# c1yc_ldm.net
KiCad netlist of a schematic drawn in Altium Designer
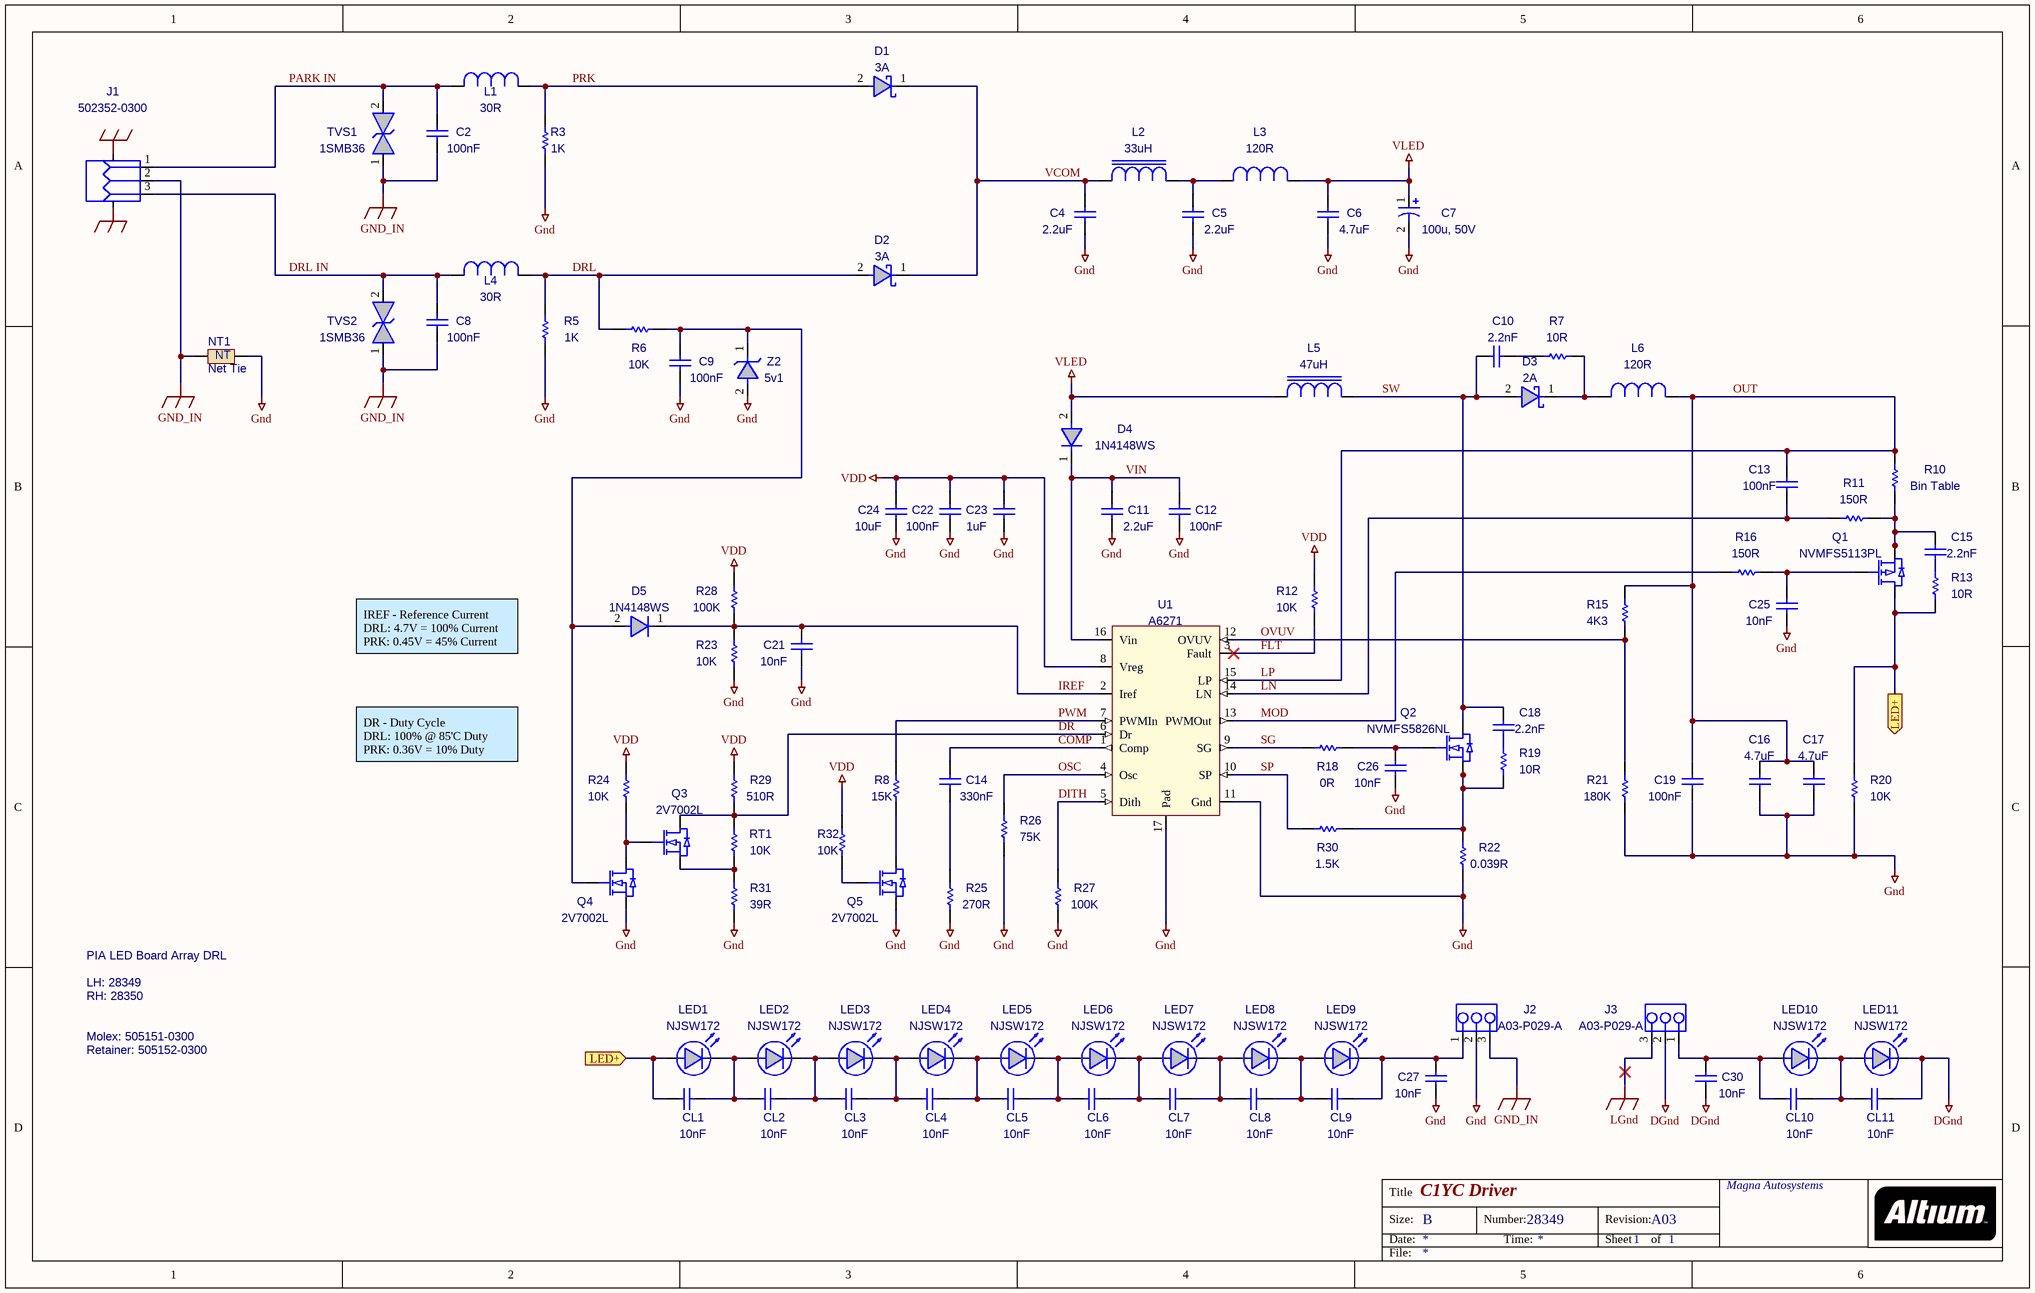
[diagram p0: c1yc_ldm.SchDoc]

(export (version "E")
  (design (tool "Eeschema 10.0.6"))
  (components
    (comp (ref "C2")
      (value "100nF")
      (footprint "CAPC0603(1608)100_N")
      (description "CAP 100nF 50V ±10% 0603 (1608 Metric) Thickness 1mm SMD")
      (fields (field (name "TOLERANCE") "±10%"))
      (libsource (lib "Altium Content Vault") (part "CMP-1035-02592-1"))
    )
    (comp (ref "C4")
      (value "2.2uF")
      (footprint "CAPC1210(3225)230_N")
      (description "CAP 2.2uF 35V ±20% 1210 (3225 Metric) Thickness 2.3mm SMD")
      (fields (field (name "TOLERANCE") "±20%"))
      (libsource (lib "Altium Content Vault") (part "CMP-1038-02095-1"))
    )
    (comp (ref "C5")
      (value "2.2uF")
      (footprint "CAPC1210(3225)230_N")
      (description "CAP 2.2uF 35V ±20% 1210 (3225 Metric) Thickness 2.3mm SMD")
      (fields (field (name "TOLERANCE") "±20%"))
      (libsource (lib "Altium Content Vault") (part "CMP-1038-02095-1"))
    )
    (comp (ref "C6")
      (value "4.7uF")
      (footprint "CAPC1210(3225)280_N")
      (description "CAP 4.7uF 50V ±10% 1210 (3225 Metric) Thickness 2.8mm SMD")
      (fields (field (name "TOLERANCE") "±10%"))
      (libsource (lib "Altium Content Vault") (part "CMP-1038-02162-1"))
    )
    (comp (ref "C7")
      (value "100u, 50V")
      (footprint "146CT1 Series 1010")
      (description "CAP ALUM 100UF 50V 20% SMD 1010")
      (libsource (lib "as_new") (part "Cap_Electro_Vishay"))
    )
    (comp (ref "C8")
      (value "100nF")
      (footprint "CAPC0603(1608)100_N")
      (description "CAP 100nF 50V ±10% 0603 (1608 Metric) Thickness 1mm SMD")
      (fields (field (name "TOLERANCE") "±10%"))
      (libsource (lib "Altium Content Vault") (part "CMP-1035-02592-1"))
    )
    (comp (ref "C9")
      (value "100nF")
      (footprint "CAPC0603(1608)100_N")
      (description "CAP 100nF 50V ±10% 0603 (1608 Metric) Thickness 1mm SMD")
      (fields (field (name "TOLERANCE") "±10%"))
      (libsource (lib "Altium Content Vault") (part "CMP-1035-02592-1"))
    )
    (comp (ref "C10")
      (value "2.2nF")
      (footprint "CAPC0603(1608)100_N")
      (description "CAP 2.2nF 50V ±10% 0603 (1608 Metric) Thickness 1mm SMD")
      (fields (field (name "TOLERANCE") "±10%"))
      (libsource (lib "Altium Content Vault") (part "CMP-1035-02039-1"))
    )
    (comp (ref "C11")
      (value "2.2uF")
      (footprint "CAPC1210(3225)230_N")
      (description "CAP 2.2uF 35V ±20% 1210 (3225 Metric) Thickness 2.3mm SMD")
      (fields (field (name "TOLERANCE") "±20%"))
      (libsource (lib "Altium Content Vault") (part "CMP-1038-02095-1"))
    )
    (comp (ref "C12")
      (value "100nF")
      (footprint "CAPC0603(1608)100_N")
      (description "CAP 100nF 50V ±10% 0603 (1608 Metric) Thickness 1mm SMD")
      (fields (field (name "TOLERANCE") "±10%"))
      (libsource (lib "Altium Content Vault") (part "CMP-1035-02592-1"))
    )
    (comp (ref "C13")
      (value "100nF")
      (footprint "CAPC0603(1608)100_N")
      (description "CAP 100nF 50V ±10% 0603 (1608 Metric) Thickness 1mm SMD")
      (fields (field (name "TOLERANCE") "±10%"))
      (libsource (lib "Altium Content Vault") (part "CMP-1035-02592-1"))
    )
    (comp (ref "C14")
      (value "330nF")
      (footprint "CAPC0603(1608)100_N")
      (description "CAP330nF 50V ±10% 0603 (1608 Metric) Thickness 1mm SMD")
      (fields (field (name "TOLERANCE") "±10%"))
      (libsource (lib "Altium Content Vault") (part "CMP-1035-02321-1"))
    )
    (comp (ref "C15")
      (value "2.2nF")
      (footprint "CAPC0603(1608)100_N")
      (description "CAP 2.2nF 50V ±10% 0603 (1608 Metric) Thickness 1mm SMD")
      (fields (field (name "TOLERANCE") "±10%"))
      (libsource (lib "Altium Content Vault") (part "CAP"))
    )
    (comp (ref "C16")
      (value "4.7uF")
      (footprint "CAPC1210(3225)280_N")
      (description "CAP 4.7uF 50V ±10% 1210 (3225 Metric) Thickness 2.8mm SMD")
      (fields (field (name "TOLERANCE") "±10%"))
      (libsource (lib "Altium Content Vault") (part "CMP-1038-02162-1"))
    )
    (comp (ref "C17")
      (value "4.7uF")
      (footprint "CAPC1210(3225)280_N")
      (description "CAP 4.7uF 50V ±10% 1210 (3225 Metric) Thickness 2.8mm SMD")
      (fields (field (name "TOLERANCE") "±10%"))
      (libsource (lib "Altium Content Vault") (part "CMP-1038-02162-1"))
    )
    (comp (ref "C18")
      (value "2.2nF")
      (footprint "CAPC0603(1608)100_N")
      (description "CAP 2.2nF 50V ±10% 0603 (1608 Metric) Thickness 1mm SMD")
      (fields (field (name "TOLERANCE") "±10%"))
      (libsource (lib "Altium Content Vault") (part "CAP"))
    )
    (comp (ref "C19")
      (value "100nF")
      (footprint "CAPC0603(1608)100_N")
      (description "CAP 100nF 50V ±10% 0603 (1608 Metric) Thickness 1mm SMD")
      (fields (field (name "TOLERANCE") "±10%"))
      (libsource (lib "Altium Content Vault") (part "CMP-1035-02592-1"))
    )
    (comp (ref "C21")
      (value "10nF")
      (footprint "CAPC0603(1608)100_N")
      (description "CAP 10nF 50V ±10% 0603 (1608 Metric) Thickness 1mm SMD")
      (fields (field (name "TOLERANCE") "±10%"))
      (libsource (lib "Altium Content Vault") (part "CMP-1035-02321-1"))
    )
    (comp (ref "C22")
      (value "100nF")
      (footprint "CAPC0603(1608)100_N")
      (description "CAP 100nF 50V ±10% 0603 (1608 Metric) Thickness 1mm SMD")
      (fields (field (name "TOLERANCE") "±10%"))
      (libsource (lib "Altium Content Vault") (part "CMP-1035-02592-1"))
    )
    (comp (ref "C23")
      (value "1uF")
      (footprint "CAPC0603(1608)100_N")
      (description "CAP 1uF 35V ±10% 0603 (1608 Metric) Thickness 1mm SMD")
      (fields (field (name "TOLERANCE") "±10%"))
      (libsource (lib "Altium Content Vault") (part "CMP-1035-02706-1"))
    )
    (comp (ref "C24")
      (value "10uF")
      (footprint "CAPC1206(3216)190_L")
      (description "CAP 10uF 16V ±10% 1206 (3216 Metric) Thickness 1.9mm SMD")
      (fields (field (name "TOLERANCE") "±10%"))
      (libsource (lib "Altium Content Vault") (part "CMP-1037-04974-1"))
    )
    (comp (ref "C25")
      (value "10nF")
      (footprint "CAPC0603(1608)100_N")
      (description "CAP 10nF 50V ±10% 0603 (1608 Metric) Thickness 1mm SMD")
      (fields (field (name "TOLERANCE") "±10%"))
      (libsource (lib "Altium Content Vault") (part "CMP-1035-02321-1"))
    )
    (comp (ref "C26")
      (value "10nF")
      (footprint "CAPC0603(1608)100_N")
      (description "CAP 10nF 50V ±10% 0603 (1608 Metric) Thickness 1mm SMD")
      (fields (field (name "TOLERANCE") "±10%"))
      (libsource (lib "Altium Content Vault") (part "CMP-1035-02321-1"))
    )
    (comp (ref "C27")
      (value "10nF")
      (footprint "CAPC0603(1608)100_N")
      (description "CAP 10nF 50V ±10% 0603 (1608 Metric) Thickness 1mm SMD")
      (fields (field (name "TOLERANCE") "±10%"))
      (libsource (lib "Altium Content Vault") (part "CMP-1035-02321-1"))
    )
    (comp (ref "C30")
      (value "10nF")
      (footprint "CAPC0603(1608)100_N")
      (description "CAP 10nF 50V ±10% 0603 (1608 Metric) Thickness 1mm SMD")
      (fields (field (name "TOLERANCE") "±10%"))
      (libsource (lib "Altium Content Vault") (part "CMP-1035-02321-1"))
    )
    (comp (ref "CL1")
      (value "10nF")
      (footprint "CAPC0603(1608)100_N")
      (description "CAP 10nF 50V ±10% 0603 (1608 Metric) Thickness 1mm SMD")
      (fields (field (name "TOLERANCE") "±10%"))
      (libsource (lib "Altium Content Vault") (part "CMP-1035-02321-1"))
    )
    (comp (ref "CL2")
      (value "10nF")
      (footprint "CAPC0603(1608)100_N")
      (description "CAP 10nF 50V ±10% 0603 (1608 Metric) Thickness 1mm SMD")
      (fields (field (name "TOLERANCE") "±10%"))
      (libsource (lib "Altium Content Vault") (part "CMP-1035-02321-1"))
    )
    (comp (ref "CL3")
      (value "10nF")
      (footprint "CAPC0603(1608)100_N")
      (description "CAP 10nF 50V ±10% 0603 (1608 Metric) Thickness 1mm SMD")
      (fields (field (name "TOLERANCE") "±10%"))
      (libsource (lib "Altium Content Vault") (part "CMP-1035-02321-1"))
    )
    (comp (ref "CL4")
      (value "10nF")
      (footprint "CAPC0603(1608)100_N")
      (description "CAP 10nF 50V ±10% 0603 (1608 Metric) Thickness 1mm SMD")
      (fields (field (name "TOLERANCE") "±10%"))
      (libsource (lib "Altium Content Vault") (part "CMP-1035-02321-1"))
    )
    (comp (ref "CL5")
      (value "10nF")
      (footprint "CAPC0603(1608)100_N")
      (description "CAP 10nF 50V ±10% 0603 (1608 Metric) Thickness 1mm SMD")
      (fields (field (name "TOLERANCE") "±10%"))
      (libsource (lib "Altium Content Vault") (part "CMP-1035-02321-1"))
    )
    (comp (ref "CL6")
      (value "10nF")
      (footprint "CAPC0603(1608)100_N")
      (description "CAP 10nF 50V ±10% 0603 (1608 Metric) Thickness 1mm SMD")
      (fields (field (name "TOLERANCE") "±10%"))
      (libsource (lib "Altium Content Vault") (part "CMP-1035-02321-1"))
    )
    (comp (ref "CL7")
      (value "10nF")
      (footprint "CAPC0603(1608)100_N")
      (description "CAP 10nF 50V ±10% 0603 (1608 Metric) Thickness 1mm SMD")
      (fields (field (name "TOLERANCE") "±10%"))
      (libsource (lib "Altium Content Vault") (part "CMP-1035-02321-1"))
    )
    (comp (ref "CL8")
      (value "10nF")
      (footprint "CAPC0603(1608)100_N")
      (description "CAP 10nF 50V ±10% 0603 (1608 Metric) Thickness 1mm SMD")
      (fields (field (name "TOLERANCE") "±10%"))
      (libsource (lib "Altium Content Vault") (part "CMP-1035-02321-1"))
    )
    (comp (ref "CL9")
      (value "10nF")
      (footprint "CAPC0603(1608)100_N")
      (description "CAP 10nF 50V ±10% 0603 (1608 Metric) Thickness 1mm SMD")
      (fields (field (name "TOLERANCE") "±10%"))
      (libsource (lib "Altium Content Vault") (part "CMP-1035-02321-1"))
    )
    (comp (ref "CL10")
      (value "10nF")
      (footprint "CAPC0603(1608)100_N")
      (description "CAP 10nF 50V ±10% 0603 (1608 Metric) Thickness 1mm SMD")
      (fields (field (name "TOLERANCE") "±10%"))
      (libsource (lib "Altium Content Vault") (part "CMP-1035-02321-1"))
    )
    (comp (ref "CL11")
      (value "10nF")
      (footprint "CAPC0603(1608)100_N")
      (description "CAP 10nF 50V ±10% 0603 (1608 Metric) Thickness 1mm SMD")
      (fields (field (name "TOLERANCE") "±10%"))
      (libsource (lib "Altium Content Vault") (part "CMP-1035-02321-1"))
    )
    (comp (ref "D1")
      (value "3A")
      (footprint "NRVBS3")
      (description "NRVBS3")
      (libsource (lib "as_new") (part "NRVBS3"))
    )
    (comp (ref "D2")
      (value "3A")
      (footprint "NRVBS3")
      (description "NRVBS3")
      (libsource (lib "as_new") (part "NRVBS3"))
    )
    (comp (ref "D3")
      (value "2A")
      (footprint "OnSemi SMB Case 403A-03")
      (description "NBRS2H")
      (libsource (lib "as_new") (part "NBRS2H"))
    )
    (comp (ref "D4") (value "1N4148WS") (footprint "SOD323F") (libsource (lib "as_new") (part "1N4148WS")))
    (comp (ref "D5") (value "1N4148WS") (footprint "SOD323F") (libsource (lib "as_new") (part "1N4148WS")))
    (comp (ref "J1")
      (value "502352-0300")
      (footprint "502352-0300")
      (description "Duraclik header, right angle SMT, 3 circuits")
      (libsource (lib "molex") (part "502352-0300"))
    )
    (comp (ref "J2")
      (value "A03-P029-A")
      (footprint "A03-P029-A")
      (description "Panta 3 pin flex ribbon")
      (libsource (lib "mech") (part "A03-P029-A"))
    )
    (comp (ref "J3")
      (value "A03-P029-A")
      (footprint "A03-P029-A")
      (description "Panta 3 pin flex ribbon")
      (libsource (lib "mech") (part "A03-P029-A"))
    )
    (comp (ref "L1")
      (value "30R")
      (footprint "BLM21PG")
      (description "Ferrite chip, 4A, 20ohm at 100 MHz, 0805 size")
      (libsource (lib "as_new") (part "BLM21PG300"))
    )
    (comp (ref "L2")
      (value "33uH")
      (footprint "CDRH127/L125")
      (description "Power Inductor")
      (libsource (lib "as_new") (part "CDRH127/L125-33u"))
    )
    (comp (ref "L3")
      (value "120R")
      (footprint "BLM21PG")
      (description "Ferrite chip, 3.0A, 120ohm at 100 MHz, 0805 size")
      (libsource (lib "as_new") (part "BLM21PG121"))
    )
    (comp (ref "L4")
      (value "30R")
      (footprint "BLM21PG")
      (description "Ferrite chip, 4A, 20ohm at 100 MHz, 0805 size")
      (libsource (lib "as_new") (part "BLM21PG300"))
    )
    (comp (ref "L5")
      (value "47uH")
      (footprint "CDRH127/L125")
      (description "Power Inductor")
      (libsource (lib "as_new") (part "CDRH127/L125-47u"))
    )
    (comp (ref "L6")
      (value "120R")
      (footprint "BLM21PG")
      (description "Ferrite chip, 3.0A, 120ohm at 100 MHz, 0805 size")
      (libsource (lib "as_new") (part "BLM21PG121"))
    )
    (comp (ref "LED1")
      (value "NJSW172")
      (footprint "NJSW172")
      (description "Nichia White LED")
      (libsource (lib "led_nichia") (part "NJSW172"))
    )
    (comp (ref "LED2")
      (value "NJSW172")
      (footprint "NJSW172")
      (description "Nichia White LED")
      (libsource (lib "led_nichia") (part "NJSW172"))
    )
    (comp (ref "LED3")
      (value "NJSW172")
      (footprint "NJSW172")
      (description "Nichia White LED")
      (libsource (lib "led_nichia") (part "NJSW172"))
    )
    (comp (ref "LED4")
      (value "NJSW172")
      (footprint "NJSW172")
      (description "Nichia White LED")
      (libsource (lib "led_nichia") (part "NJSW172"))
    )
    (comp (ref "LED5")
      (value "NJSW172")
      (footprint "NJSW172")
      (description "Nichia White LED")
      (libsource (lib "led_nichia") (part "NJSW172"))
    )
    (comp (ref "LED6")
      (value "NJSW172")
      (footprint "NJSW172")
      (description "Nichia White LED")
      (libsource (lib "led_nichia") (part "NJSW172"))
    )
    (comp (ref "LED7")
      (value "NJSW172")
      (footprint "NJSW172")
      (description "Nichia White LED")
      (libsource (lib "led_nichia") (part "NJSW172"))
    )
    (comp (ref "LED8")
      (value "NJSW172")
      (footprint "NJSW172")
      (description "Nichia White LED")
      (libsource (lib "led_nichia") (part "NJSW172"))
    )
    (comp (ref "LED9")
      (value "NJSW172")
      (footprint "NJSW172")
      (description "Nichia White LED")
      (libsource (lib "led_nichia") (part "NJSW172"))
    )
    (comp (ref "LED10")
      (value "NJSW172")
      (footprint "NJSW172")
      (description "Nichia White LED")
      (libsource (lib "led_nichia") (part "NJSW172"))
    )
    (comp (ref "LED11")
      (value "NJSW172")
      (footprint "NJSW172")
      (description "Nichia White LED")
      (libsource (lib "led_nichia") (part "NJSW172"))
    )
    (comp (ref "NT1")
      (value "Net Tie")
      (footprint "Net_Tie_SMT_1mm")
      (libsource (lib "as_new") (part "Net_Tie"))
    )
    (comp (ref "Q1")
      (value "NVMFS5113PL")
      (footprint "ONSEMI DFN5 5x6 CASE 488AA Issue H")
      (description "P Channel Mosfet, 60V, 64A")
      (libsource (lib "as_new") (part "NVMFS5113PL"))
    )
    (comp (ref "Q2")
      (value "NVMFS5826NL")
      (footprint "ONSEMI DFN5 5x6 CASE 488AA Issue H")
      (description "N Channel Mosfet, 60V, 26A")
      (libsource (lib "as_new") (part "NVMFS5826NL"))
    )
    (comp (ref "Q3")
      (value "2V7002L")
      (footprint "OnSemi SOT-23 Case 318-08 Issue AP")
      (description "N Channel Mosfet, 60V, 100mA")
      (libsource (lib "as_new") (part "2V7002L"))
    )
    (comp (ref "Q4")
      (value "2V7002L")
      (footprint "OnSemi SOT-23 Case 318-08 Issue AP")
      (description "N Channel Mosfet, 60V, 100mA")
      (libsource (lib "as_new") (part "2V7002L"))
    )
    (comp (ref "Q5")
      (value "2V7002L")
      (footprint "OnSemi SOT-23 Case 318-08 Issue AP")
      (description "N Channel Mosfet, 60V, 100mA")
      (libsource (lib "as_new") (part "2V7002L"))
    )
    (comp (ref "R3")
      (value "1K")
      (footprint "RESC1206(3216)_N")
      (description "1K 0.25W 1% 1206 (3216 Metric)  SMD")
      (fields (field (name "TOLERANCE") "1 %") (field (name "POWER") "0.25 W"))
      (libsource (lib "Altium Content Vault") (part "CMP-1014-00510-1"))
    )
    (comp (ref "R5")
      (value "1K")
      (footprint "RESC1206(3216)_N")
      (description "1K 0.25W 1% 1206 (3216 Metric)  SMD")
      (fields (field (name "TOLERANCE") "1 %") (field (name "POWER") "0.25 W"))
      (libsource (lib "Altium Content Vault") (part "CMP-1014-00510-1"))
    )
    (comp (ref "R6")
      (value "10K")
      (footprint "RESC0603(1608)_N")
      (description "10K 0.1W 1% 0603 (1608 Metric)  SMD")
      (fields (field (name "TOLERANCE") "1 %"))
      (libsource (lib "Altium Content Vault") (part "CMP-1012-00623-1"))
    )
    (comp (ref "R7")
      (value "10R")
      (footprint "RESC0603(1608)_N")
      (description "10R 0.1W 1% 0603 (1608 Metric)  SMD")
      (fields (field (name "TOLERANCE") "1 %"))
      (libsource (lib "Altium Content Vault") (part "CMP-1012-00284-1"))
    )
    (comp (ref "R8")
      (value "15K")
      (footprint "RESC0603(1608)_N")
      (description "15K 0.1W 1% 0603 (1608 Metric)  SMD")
      (fields (field (name "TOLERANCE") "1 %"))
      (libsource (lib "Altium Content Vault") (part "CMP-1012-00623-1"))
    )
    (comp (ref "R10")
      (value "Bin Table")
      (footprint "RESC0805(2012)_N")
      (description "Jumper 0805 (2012 Metric)")
      (fields (field (name "TOLERANCE") "None"))
      (libsource (lib "Altium Content Vault") (part "CMP-1013-00001-1"))
    )
    (comp (ref "R11")
      (value "150R")
      (footprint "RESC0603(1608)_N")
      (description "150R 0.1W 1% 0603 (1608 Metric)  SMD")
      (fields (field (name "TOLERANCE") "1 %") (field (name "POWER") "0.1 W"))
      (libsource (lib "Altium Content Vault") (part "CMP-1012-00415-1"))
    )
    (comp (ref "R12")
      (value "10K")
      (footprint "RESC0603(1608)_N")
      (description "10K 0.1W 1% 0603 (1608 Metric)  SMD")
      (fields (field (name "TOLERANCE") "1 %"))
      (libsource (lib "Altium Content Vault") (part "CMP-1012-00623-1"))
    )
    (comp (ref "R13")
      (value "10R")
      (footprint "RESC0603(1608)_N")
      (description "10R 0.1W 1% 0603 (1608 Metric)  SMD")
      (fields (field (name "TOLERANCE") "1 %"))
      (libsource (lib "Altium Content Vault") (part "CMP-1012-00284-1"))
    )
    (comp (ref "R15")
      (value "4K3")
      (footprint "RESC0603(1608)_N")
      (description "4K3 0.1W 1% 0603 (1608 Metric)  SMD")
      (fields (field (name "TOLERANCE") "1 %"))
      (libsource (lib "Altium Content Vault") (part "CMP-1012-00623-1"))
    )
    (comp (ref "R16")
      (value "150R")
      (footprint "RESC0603(1608)_N")
      (description "150R 0.1W 1% 0603 (1608 Metric)  SMD")
      (fields (field (name "TOLERANCE") "1 %") (field (name "POWER") "0.1 W"))
      (libsource (lib "Altium Content Vault") (part "CMP-1012-00415-1"))
    )
    (comp (ref "R18")
      (value "0R")
      (footprint "RESC0603(1608)_N")
      (description "0R 0.1W 1% 0603 (1608 Metric)  SMD")
      (fields (field (name "TOLERANCE") "1 %") (field (name "POWER") "0.1 W"))
      (libsource (lib "Altium Content Vault") (part "CMP-1012-00415-1"))
    )
    (comp (ref "R19")
      (value "10R")
      (footprint "RESC0603(1608)_N")
      (description "10R 0.1W 1% 0603 (1608 Metric)  SMD")
      (fields (field (name "TOLERANCE") "1 %"))
      (libsource (lib "Altium Content Vault") (part "CMP-1012-00284-1"))
    )
    (comp (ref "R20")
      (value "10K")
      (footprint "RESC0603(1608)_N")
      (description "10K 0.1W 1% 0603 (1608 Metric)  SMD")
      (fields (field (name "TOLERANCE") "1 %"))
      (libsource (lib "Altium Content Vault") (part "CMP-1012-00623-1"))
    )
    (comp (ref "R21")
      (value "180K")
      (footprint "RESC0603(1608)_N")
      (description "180K 0.1W 1% 0603 (1608 Metric)  SMD")
      (fields (field (name "TOLERANCE") "1 %"))
      (libsource (lib "Altium Content Vault") (part "CMP-1012-00623-1"))
    )
    (comp (ref "R22")
      (value "0.039R")
      (footprint "RESC0805(2012)_N")
      (description "Jumper 0805 (2012 Metric)")
      (fields (field (name "TOLERANCE") "None"))
      (libsource (lib "Altium Content Vault") (part "CMP-1013-00001-1"))
    )
    (comp (ref "R23")
      (value "10K")
      (footprint "RESC0603(1608)_N")
      (description "10K 0.1W 1% 0603 (1608 Metric)  SMD")
      (fields (field (name "TOLERANCE") "1 %"))
      (libsource (lib "Altium Content Vault") (part "CMP-1012-00623-1"))
    )
    (comp (ref "R24")
      (value "10K")
      (footprint "RESC0603(1608)_N")
      (description "10K 0.1W 1% 0603 (1608 Metric)  SMD")
      (fields (field (name "TOLERANCE") "1 %"))
      (libsource (lib "Altium Content Vault") (part "CMP-1012-00623-1"))
    )
    (comp (ref "R25")
      (value "270R")
      (footprint "RESC0603(1608)_N")
      (description "270R 0.1W 1% 0603 (1608 Metric)  SMD")
      (fields (field (name "TOLERANCE") "1 %"))
      (libsource (lib "Altium Content Vault") (part "CMP-1012-00623-1"))
    )
    (comp (ref "R26")
      (value "75K")
      (footprint "RESC0603(1608)_N")
      (description "75K 0.1W 1% 0603 (1608 Metric)  SMD")
      (fields (field (name "TOLERANCE") "1 %") (field (name "POWER") "0.1 W"))
      (libsource (lib "Altium Content Vault") (part "CMP-1012-00712-1"))
    )
    (comp (ref "R27")
      (value "100K")
      (footprint "RESC0603(1608)_N")
      (description "62K 0.1W 1% 0603 (1608 Metric)  SMD")
      (fields (field (name "TOLERANCE") "1 %") (field (name "POWER") "0.1 W"))
      (libsource (lib "Altium Content Vault") (part "CMP-1012-00712-1"))
    )
    (comp (ref "R28")
      (value "100K")
      (footprint "RESC0603(1608)_N")
      (description "100K 0.1W 1% 0603 (1608 Metric)  SMD")
      (fields (field (name "TOLERANCE") "1 %"))
      (libsource (lib "Altium Content Vault") (part "CMP-1012-00623-1"))
    )
    (comp (ref "R29")
      (value "510R")
      (footprint "RESC0603(1608)_N")
      (description "510R 0.1W 1% 0603 (1608 Metric)  SMD")
      (fields (field (name "TOLERANCE") "1 %"))
      (libsource (lib "Altium Content Vault") (part "CMP-1012-00623-1"))
    )
    (comp (ref "R30")
      (value "1.5K")
      (footprint "RESC0603(1608)_N")
      (description "1.5K 0.1W 1% 0603 (1608 Metric)  SMD")
      (fields (field (name "TOLERANCE") "1 %") (field (name "POWER") "0.1 W"))
      (libsource (lib "Altium Content Vault") (part "CMP-1012-00415-1"))
    )
    (comp (ref "R31")
      (value "39R")
      (footprint "RESC0603(1608)_N")
      (description "39R 0.1W 1% 0603 (1608 Metric)  SMD")
      (fields (field (name "TOLERANCE") "1 %"))
      (libsource (lib "Altium Content Vault") (part "CMP-1012-00623-1"))
    )
    (comp (ref "R32")
      (value "10K")
      (footprint "RESC0603(1608)_N")
      (description "10K 0.1W 1% 0603 (1608 Metric)  SMD")
      (fields (field (name "TOLERANCE") "1 %"))
      (libsource (lib "Altium Content Vault") (part "CMP-1012-00623-1"))
    )
    (comp (ref "RT1")
      (value "10K")
      (footprint "RESC0603(1608)_N")
      (description "10K 0.1W 1% 0603 Thermistor")
      (fields (field (name "TOLERANCE") "1 %"))
      (libsource (lib "Altium Content Vault") (part "CMP-1012-00623-1"))
    )
    (comp (ref "TVS1")
      (value "1SMB36")
      (footprint "OnSemi SMB Case 403C-01")
      (description "TVS 600W, 36V")
      (libsource (lib "as_new") (part "1SMB36"))
    )
    (comp (ref "TVS2")
      (value "1SMB36")
      (footprint "OnSemi SMB Case 403C-01")
      (description "TVS 600W, 36V")
      (libsource (lib "as_new") (part "1SMB36"))
    )
    (comp (ref "U1")
      (value "A6271")
      (footprint "A6268_LP")
      (description "High Current LED Buck Boost Controller")
      (libsource (lib "as_new") (part "A6271"))
    )
    (comp (ref "Z2")
      (value "5v1")
      (footprint "MM3Z")
      (description "Zener Diode, SOD323, 5.1v, 200 mW")
      (libsource (lib "as_new") (part "MM3Z5V1"))
    )
  )
  (nets
    (net (code "1") (name "/COMP") (class "Default")
      (node (ref "C14") (pin "2") (pinfunction "2_2") (pintype "passive"))
      (node (ref "U1") (pin "1") (pinfunction "Comp_1") (pintype "output"))
    )
    (net (code "2") (name "/DITH") (class "Default")
      (node (ref "R27") (pin "2") (pinfunction "2_2") (pintype "passive"))
      (node (ref "U1") (pin "5") (pinfunction "Dith_5") (pintype "input"))
    )
    (net (code "3") (name "/DR") (class "Default")
      (node (ref "Q3") (pin "3") (pinfunction "D_3") (pintype "passive"))
      (node (ref "R29") (pin "1") (pinfunction "1_1") (pintype "passive"))
      (node (ref "RT1") (pin "2") (pinfunction "2_2") (pintype "passive"))
      (node (ref "U1") (pin "6") (pinfunction "Dr_6") (pintype "input"))
    )
    (net (code "4") (name "/DRL") (class "Default")
      (node (ref "D2") (pin "2") (pinfunction "A_2") (pintype "passive"))
      (node (ref "L4") (pin "1") (pintype "passive"))
      (node (ref "R5") (pin "2") (pinfunction "2_2") (pintype "passive"))
      (node (ref "R6") (pin "2") (pinfunction "2_2") (pintype "passive"))
    )
    (net (code "5") (name "/DRL IN") (class "Default")
      (node (ref "C8") (pin "2") (pinfunction "2_2") (pintype "passive"))
      (node (ref "J1") (pin "3") (pinfunction "3_3") (pintype "passive"))
      (node (ref "L4") (pin "2") (pintype "passive"))
      (node (ref "TVS2") (pin "2") (pintype "passive"))
    )
    (net (code "6") (name "/FLT") (class "Default")
      (node (ref "R12") (pin "1") (pinfunction "1_1") (pintype "passive"))
      (node (ref "U1") (pin "3") (pinfunction "Fault_3") (pintype "open_collector"))
    )
    (net (code "7") (name "/IREF") (class "Default")
      (node (ref "C21") (pin "2") (pinfunction "2_2") (pintype "passive"))
      (node (ref "D5") (pin "1") (pintype "passive"))
      (node (ref "R23") (pin "2") (pinfunction "2_2") (pintype "passive"))
      (node (ref "R28") (pin "1") (pinfunction "1_1") (pintype "passive"))
      (node (ref "U1") (pin "2") (pinfunction "Iref_2") (pintype "power_in"))
    )
    (net (code "8") (name "/LED+") (class "Default")
      (node (ref "CL1") (pin "2") (pinfunction "2_2") (pintype "passive"))
      (node (ref "LED1") (pin "2") (pinfunction "Anode_2") (pintype "passive"))
      (node (ref "Q1") (pin "5") (pinfunction "D_5") (pintype "passive"))
      (node (ref "R13") (pin "2") (pinfunction "2_2") (pintype "passive"))
      (node (ref "R20") (pin "2") (pinfunction "2_2") (pintype "passive"))
    )
    (net (code "9") (name "/LN") (class "Default")
      (node (ref "C13") (pin "1") (pinfunction "1_1") (pintype "passive"))
      (node (ref "R11") (pin "1") (pinfunction "1_1") (pintype "passive"))
      (node (ref "U1") (pin "14") (pinfunction "LN_14") (pintype "input"))
    )
    (net (code "10") (name "/LP") (class "Default")
      (node (ref "C13") (pin "2") (pinfunction "2_2") (pintype "passive"))
      (node (ref "C16") (pin "2") (pinfunction "2_2") (pintype "passive"))
      (node (ref "C17") (pin "2") (pinfunction "2_2") (pintype "passive"))
      (node (ref "C19") (pin "2") (pinfunction "2_2") (pintype "passive"))
      (node (ref "L6") (pin "1") (pintype "passive"))
      (node (ref "R10") (pin "2") (pinfunction "2_2") (pintype "passive"))
      (node (ref "R15") (pin "2") (pinfunction "2_2") (pintype "passive"))
      (node (ref "U1") (pin "15") (pinfunction "LP_15") (pintype "input"))
    )
    (net (code "11") (name "/MOD") (class "Default")
      (node (ref "R16") (pin "1") (pinfunction "1_1") (pintype "passive"))
      (node (ref "U1") (pin "13") (pinfunction "PWMOut_13") (pintype "output"))
    )
    (net (code "12") (name "/OSC") (class "Default")
      (node (ref "R26") (pin "2") (pinfunction "2_2") (pintype "passive"))
      (node (ref "U1") (pin "4") (pinfunction "Osc_4") (pintype "input"))
    )
    (net (code "13") (name "/OVUV") (class "Default")
      (node (ref "R15") (pin "1") (pinfunction "1_1") (pintype "passive"))
      (node (ref "R21") (pin "2") (pinfunction "2_2") (pintype "passive"))
      (node (ref "U1") (pin "12") (pinfunction "OVUV_12") (pintype "input"))
    )
    (net (code "14") (name "/PARK IN") (class "Default")
      (node (ref "C2") (pin "2") (pinfunction "2_2") (pintype "passive"))
      (node (ref "J1") (pin "1") (pinfunction "1_1") (pintype "passive"))
      (node (ref "L1") (pin "2") (pintype "passive"))
      (node (ref "TVS1") (pin "2") (pintype "passive"))
    )
    (net (code "15") (name "/PRK") (class "Default")
      (node (ref "D1") (pin "2") (pinfunction "A_2") (pintype "passive"))
      (node (ref "L1") (pin "1") (pintype "passive"))
      (node (ref "R3") (pin "2") (pinfunction "2_2") (pintype "passive"))
    )
    (net (code "16") (name "/PWM") (class "Default")
      (node (ref "R8") (pin "2") (pinfunction "2_2") (pintype "passive"))
      (node (ref "U1") (pin "7") (pinfunction "PWMIn_7") (pintype "input"))
    )
    (net (code "17") (name "/SG") (class "Default")
      (node (ref "R18") (pin "1") (pinfunction "1_1") (pintype "passive"))
      (node (ref "U1") (pin "9") (pinfunction "SG_9") (pintype "output"))
    )
    (net (code "18") (name "/SP") (class "Default")
      (node (ref "R30") (pin "1") (pinfunction "1_1") (pintype "passive"))
      (node (ref "U1") (pin "10") (pinfunction "SP_10") (pintype "input"))
    )
    (net (code "19") (name "/SW") (class "Default")
      (node (ref "C10") (pin "2") (pinfunction "2_2") (pintype "passive"))
      (node (ref "C18") (pin "1") (pinfunction "1_1") (pintype "passive"))
      (node (ref "D3") (pin "2") (pinfunction "A_2") (pintype "passive"))
      (node (ref "L5") (pin "1") (pintype "passive"))
      (node (ref "Q2") (pin "5") (pinfunction "D_5") (pintype "passive"))
    )
    (net (code "20") (name "/VCOM") (class "Default")
      (node (ref "C4") (pin "2") (pinfunction "2_2") (pintype "passive"))
      (node (ref "D1") (pin "1") (pinfunction "C_1") (pintype "passive"))
      (node (ref "D2") (pin "1") (pinfunction "C_1") (pintype "passive"))
      (node (ref "L2") (pin "2") (pintype "passive"))
    )
    (net (code "21") (name "/VIN") (class "Default")
      (node (ref "C11") (pin "2") (pinfunction "2_2") (pintype "passive"))
      (node (ref "C12") (pin "2") (pinfunction "2_2") (pintype "passive"))
      (node (ref "D4") (pin "1") (pintype "passive"))
      (node (ref "U1") (pin "16") (pinfunction "Vin_16") (pintype "power_in"))
    )
    (net (code "22") (name "DGnd") (class "Default")
      (node (ref "C30") (pin "1") (pinfunction "1_1") (pintype "passive"))
      (node (ref "CL11") (pin "1") (pinfunction "1_1") (pintype "passive"))
      (node (ref "J3") (pin "2") (pinfunction "2_2") (pintype "passive"))
      (node (ref "LED11") (pin "1") (pinfunction "Cathode_1") (pintype "passive"))
    )
    (net (code "23") (name "GND_IN") (class "Default")
      (node (ref "C2") (pin "1") (pinfunction "1_1") (pintype "passive"))
      (node (ref "C8") (pin "1") (pinfunction "1_1") (pintype "passive"))
      (node (ref "J1") (pin "2") (pinfunction "2_2") (pintype "passive"))
      (node (ref "J1") (pin "4") (pinfunction "4_4") (pintype "passive"))
      (node (ref "J1") (pin "5") (pinfunction "5_5") (pintype "passive"))
      (node (ref "J2") (pin "3") (pinfunction "3_3") (pintype "passive"))
      (node (ref "NT1") (pin "1") (pinfunction "1_1") (pintype "power_in"))
      (node (ref "TVS1") (pin "1") (pintype "passive"))
      (node (ref "TVS2") (pin "1") (pintype "passive"))
    )
    (net (code "24") (name "Gnd") (class "Default")
      (node (ref "C11") (pin "1") (pinfunction "1_1") (pintype "passive"))
      (node (ref "C12") (pin "1") (pinfunction "1_1") (pintype "passive"))
      (node (ref "C16") (pin "1") (pinfunction "1_1") (pintype "passive"))
      (node (ref "C17") (pin "1") (pinfunction "1_1") (pintype "passive"))
      (node (ref "C19") (pin "1") (pinfunction "1_1") (pintype "passive"))
      (node (ref "C21") (pin "1") (pinfunction "1_1") (pintype "passive"))
      (node (ref "C22") (pin "1") (pinfunction "1_1") (pintype "passive"))
      (node (ref "C23") (pin "1") (pinfunction "1_1") (pintype "passive"))
      (node (ref "C24") (pin "1") (pinfunction "1_1") (pintype "passive"))
      (node (ref "C25") (pin "1") (pinfunction "1_1") (pintype "passive"))
      (node (ref "C26") (pin "1") (pinfunction "1_1") (pintype "passive"))
      (node (ref "C27") (pin "1") (pinfunction "1_1") (pintype "passive"))
      (node (ref "C4") (pin "1") (pinfunction "1_1") (pintype "passive"))
      (node (ref "C5") (pin "1") (pinfunction "1_1") (pintype "passive"))
      (node (ref "C6") (pin "1") (pinfunction "1_1") (pintype "passive"))
      (node (ref "C7") (pin "2") (pinfunction "-_2") (pintype "passive"))
      (node (ref "C9") (pin "1") (pinfunction "1_1") (pintype "passive"))
      (node (ref "J2") (pin "2") (pinfunction "2_2") (pintype "passive"))
      (node (ref "NT1") (pin "2") (pinfunction "2_2") (pintype "power_in"))
      (node (ref "Q4") (pin "2") (pinfunction "S_2") (pintype "passive"))
      (node (ref "Q5") (pin "2") (pinfunction "S_2") (pintype "passive"))
      (node (ref "R20") (pin "1") (pinfunction "1_1") (pintype "passive"))
      (node (ref "R21") (pin "1") (pinfunction "1_1") (pintype "passive"))
      (node (ref "R22") (pin "1") (pinfunction "1_1") (pintype "passive"))
      (node (ref "R23") (pin "1") (pinfunction "1_1") (pintype "passive"))
      (node (ref "R25") (pin "1") (pinfunction "1_1") (pintype "passive"))
      (node (ref "R26") (pin "1") (pinfunction "1_1") (pintype "passive"))
      (node (ref "R27") (pin "1") (pinfunction "1_1") (pintype "passive"))
      (node (ref "R3") (pin "1") (pinfunction "1_1") (pintype "passive"))
      (node (ref "R31") (pin "1") (pinfunction "1_1") (pintype "passive"))
      (node (ref "R5") (pin "1") (pinfunction "1_1") (pintype "passive"))
      (node (ref "U1") (pin "11") (pinfunction "Gnd_11") (pintype "power_in"))
      (node (ref "U1") (pin "17") (pinfunction "Pad_17") (pintype "passive"))
      (node (ref "Z2") (pin "2") (pintype "passive"))
    )
    (net (code "25") (name "LGnd") (class "Default")
      (node (ref "J3") (pin "3") (pinfunction "3_3") (pintype "passive"))
    )
    (net (code "26") (name "Net-(C5-Pad2)") (class "Default")
      (node (ref "C5") (pin "2") (pinfunction "2_2") (pintype "passive"))
      (node (ref "L2") (pin "1") (pintype "passive"))
      (node (ref "L3") (pin "2") (pintype "passive"))
    )
    (net (code "27") (name "Net-(C10-Pad1)") (class "Default")
      (node (ref "C10") (pin "1") (pinfunction "1_1") (pintype "passive"))
      (node (ref "R7") (pin "2") (pinfunction "2_2") (pintype "passive"))
    )
    (net (code "28") (name "Net-(C14-Pad1)") (class "Default")
      (node (ref "C14") (pin "1") (pinfunction "1_1") (pintype "passive"))
      (node (ref "R25") (pin "2") (pinfunction "2_2") (pintype "passive"))
    )
    (net (code "29") (name "Net-(C15-Pad1)") (class "Default")
      (node (ref "C15") (pin "1") (pinfunction "1_1") (pintype "passive"))
      (node (ref "Q1") (pin "1") (pinfunction "S_1") (pintype "passive"))
      (node (ref "Q1") (pin "2") (pinfunction "S_2") (pintype "passive"))
      (node (ref "Q1") (pin "3") (pinfunction "S_3") (pintype "passive"))
      (node (ref "R10") (pin "1") (pinfunction "1_1") (pintype "passive"))
      (node (ref "R11") (pin "2") (pinfunction "2_2") (pintype "passive"))
    )
    (net (code "30") (name "Net-(C15-Pad2)") (class "Default")
      (node (ref "C15") (pin "2") (pinfunction "2_2") (pintype "passive"))
      (node (ref "R13") (pin "1") (pinfunction "1_1") (pintype "passive"))
    )
    (net (code "31") (name "Net-(C18-Pad2)") (class "Default")
      (node (ref "C18") (pin "2") (pinfunction "2_2") (pintype "passive"))
      (node (ref "R19") (pin "1") (pinfunction "1_1") (pintype "passive"))
    )
    (net (code "32") (name "Net-(D3-C)") (class "Default")
      (node (ref "D3") (pin "1") (pinfunction "C_1") (pintype "passive"))
      (node (ref "L6") (pin "2") (pintype "passive"))
      (node (ref "R7") (pin "1") (pinfunction "1_1") (pintype "passive"))
    )
    (net (code "33") (name "Net-(LED1-Cathode)") (class "Default")
      (node (ref "CL1") (pin "1") (pinfunction "1_1") (pintype "passive"))
      (node (ref "CL2") (pin "2") (pinfunction "2_2") (pintype "passive"))
      (node (ref "LED1") (pin "1") (pinfunction "Cathode_1") (pintype "passive"))
      (node (ref "LED2") (pin "2") (pinfunction "Anode_2") (pintype "passive"))
    )
    (net (code "34") (name "Net-(LED2-Cathode)") (class "Default")
      (node (ref "CL2") (pin "1") (pinfunction "1_1") (pintype "passive"))
      (node (ref "CL3") (pin "2") (pinfunction "2_2") (pintype "passive"))
      (node (ref "LED2") (pin "1") (pinfunction "Cathode_1") (pintype "passive"))
      (node (ref "LED3") (pin "2") (pinfunction "Anode_2") (pintype "passive"))
    )
    (net (code "35") (name "Net-(LED3-Cathode)") (class "Default")
      (node (ref "CL3") (pin "1") (pinfunction "1_1") (pintype "passive"))
      (node (ref "CL4") (pin "2") (pinfunction "2_2") (pintype "passive"))
      (node (ref "LED3") (pin "1") (pinfunction "Cathode_1") (pintype "passive"))
      (node (ref "LED4") (pin "2") (pinfunction "Anode_2") (pintype "passive"))
    )
    (net (code "36") (name "Net-(LED4-Cathode)") (class "Default")
      (node (ref "CL4") (pin "1") (pinfunction "1_1") (pintype "passive"))
      (node (ref "CL5") (pin "2") (pinfunction "2_2") (pintype "passive"))
      (node (ref "LED4") (pin "1") (pinfunction "Cathode_1") (pintype "passive"))
      (node (ref "LED5") (pin "2") (pinfunction "Anode_2") (pintype "passive"))
    )
    (net (code "37") (name "Net-(LED5-Cathode)") (class "Default")
      (node (ref "CL5") (pin "1") (pinfunction "1_1") (pintype "passive"))
      (node (ref "CL6") (pin "2") (pinfunction "2_2") (pintype "passive"))
      (node (ref "LED5") (pin "1") (pinfunction "Cathode_1") (pintype "passive"))
      (node (ref "LED6") (pin "2") (pinfunction "Anode_2") (pintype "passive"))
    )
    (net (code "38") (name "Net-(LED6-Cathode)") (class "Default")
      (node (ref "CL6") (pin "1") (pinfunction "1_1") (pintype "passive"))
      (node (ref "CL7") (pin "2") (pinfunction "2_2") (pintype "passive"))
      (node (ref "LED6") (pin "1") (pinfunction "Cathode_1") (pintype "passive"))
      (node (ref "LED7") (pin "2") (pinfunction "Anode_2") (pintype "passive"))
    )
    (net (code "39") (name "Net-(LED7-Cathode)") (class "Default")
      (node (ref "CL7") (pin "1") (pinfunction "1_1") (pintype "passive"))
      (node (ref "CL8") (pin "2") (pinfunction "2_2") (pintype "passive"))
      (node (ref "LED7") (pin "1") (pinfunction "Cathode_1") (pintype "passive"))
      (node (ref "LED8") (pin "2") (pinfunction "Anode_2") (pintype "passive"))
    )
    (net (code "40") (name "Net-(LED8-Cathode)") (class "Default")
      (node (ref "CL8") (pin "1") (pinfunction "1_1") (pintype "passive"))
      (node (ref "CL9") (pin "2") (pinfunction "2_2") (pintype "passive"))
      (node (ref "LED8") (pin "1") (pinfunction "Cathode_1") (pintype "passive"))
      (node (ref "LED9") (pin "2") (pinfunction "Anode_2") (pintype "passive"))
    )
    (net (code "41") (name "Net-(LED9-Cathode)") (class "Default")
      (node (ref "C27") (pin "2") (pinfunction "2_2") (pintype "passive"))
      (node (ref "CL9") (pin "1") (pinfunction "1_1") (pintype "passive"))
      (node (ref "J2") (pin "1") (pinfunction "1_1") (pintype "passive"))
      (node (ref "LED9") (pin "1") (pinfunction "Cathode_1") (pintype "passive"))
    )
    (net (code "42") (name "Net-(LED10-Anode)") (class "Default")
      (node (ref "C30") (pin "2") (pinfunction "2_2") (pintype "passive"))
      (node (ref "CL10") (pin "2") (pinfunction "2_2") (pintype "passive"))
      (node (ref "J3") (pin "1") (pinfunction "1_1") (pintype "passive"))
      (node (ref "LED10") (pin "2") (pinfunction "Anode_2") (pintype "passive"))
    )
    (net (code "43") (name "Net-(LED10-Cathode)") (class "Default")
      (node (ref "CL10") (pin "1") (pinfunction "1_1") (pintype "passive"))
      (node (ref "CL11") (pin "2") (pinfunction "2_2") (pintype "passive"))
      (node (ref "LED10") (pin "1") (pinfunction "Cathode_1") (pintype "passive"))
      (node (ref "LED11") (pin "2") (pinfunction "Anode_2") (pintype "passive"))
    )
    (net (code "44") (name "Net-(Q1-G)") (class "Default")
      (node (ref "C25") (pin "2") (pinfunction "2_2") (pintype "passive"))
      (node (ref "Q1") (pin "4") (pinfunction "G_4") (pintype "passive"))
      (node (ref "R16") (pin "2") (pinfunction "2_2") (pintype "passive"))
    )
    (net (code "45") (name "Net-(Q2-G)") (class "Default")
      (node (ref "C26") (pin "2") (pinfunction "2_2") (pintype "passive"))
      (node (ref "Q2") (pin "4") (pinfunction "G_4") (pintype "passive"))
      (node (ref "R18") (pin "2") (pinfunction "2_2") (pintype "passive"))
    )
    (net (code "46") (name "Net-(Q2-S-Pad1)") (class "Default")
      (node (ref "Q2") (pin "1") (pinfunction "S_1") (pintype "passive"))
      (node (ref "Q2") (pin "2") (pinfunction "S_2") (pintype "passive"))
      (node (ref "Q2") (pin "3") (pinfunction "S_3") (pintype "passive"))
      (node (ref "R19") (pin "2") (pinfunction "2_2") (pintype "passive"))
      (node (ref "R22") (pin "2") (pinfunction "2_2") (pintype "passive"))
      (node (ref "R30") (pin "2") (pinfunction "2_2") (pintype "passive"))
    )
    (net (code "47") (name "Net-(Q3-G)") (class "Default")
      (node (ref "Q3") (pin "1") (pinfunction "G_1") (pintype "passive"))
      (node (ref "Q4") (pin "3") (pinfunction "D_3") (pintype "passive"))
      (node (ref "R24") (pin "1") (pinfunction "1_1") (pintype "passive"))
    )
    (net (code "48") (name "Net-(Q3-S)") (class "Default")
      (node (ref "Q3") (pin "2") (pinfunction "S_2") (pintype "passive"))
      (node (ref "R31") (pin "2") (pinfunction "2_2") (pintype "passive"))
      (node (ref "RT1") (pin "1") (pinfunction "1_1") (pintype "passive"))
    )
    (net (code "49") (name "Net-(Q4-G)") (class "Default")
      (node (ref "C9") (pin "2") (pinfunction "2_2") (pintype "passive"))
      (node (ref "D5") (pin "2") (pintype "passive"))
      (node (ref "Q4") (pin "1") (pinfunction "G_1") (pintype "passive"))
      (node (ref "R6") (pin "1") (pinfunction "1_1") (pintype "passive"))
      (node (ref "Z2") (pin "1") (pintype "passive"))
    )
    (net (code "50") (name "Net-(Q5-D)") (class "Default")
      (node (ref "Q5") (pin "3") (pinfunction "D_3") (pintype "passive"))
      (node (ref "R8") (pin "1") (pinfunction "1_1") (pintype "passive"))
    )
    (net (code "51") (name "Net-(Q5-G)") (class "Default")
      (node (ref "Q5") (pin "1") (pinfunction "G_1") (pintype "passive"))
      (node (ref "R32") (pin "1") (pinfunction "1_1") (pintype "passive"))
    )
    (net (code "52") (name "VDD") (class "Default")
      (node (ref "C22") (pin "2") (pinfunction "2_2") (pintype "passive"))
      (node (ref "C23") (pin "2") (pinfunction "2_2") (pintype "passive"))
      (node (ref "C24") (pin "2") (pinfunction "2_2") (pintype "passive"))
      (node (ref "R12") (pin "2") (pinfunction "2_2") (pintype "passive"))
      (node (ref "R24") (pin "2") (pinfunction "2_2") (pintype "passive"))
      (node (ref "R28") (pin "2") (pinfunction "2_2") (pintype "passive"))
      (node (ref "R29") (pin "2") (pinfunction "2_2") (pintype "passive"))
      (node (ref "R32") (pin "2") (pinfunction "2_2") (pintype "passive"))
      (node (ref "U1") (pin "8") (pinfunction "Vreg_8") (pintype "power_in"))
    )
    (net (code "53") (name "VLED") (class "Default")
      (node (ref "C6") (pin "2") (pinfunction "2_2") (pintype "passive"))
      (node (ref "C7") (pin "1") (pinfunction "+_1") (pintype "passive"))
      (node (ref "D4") (pin "2") (pintype "passive"))
      (node (ref "L3") (pin "1") (pintype "passive"))
      (node (ref "L5") (pin "2") (pintype "passive"))
    )
  )
)
